# Optocouplers.net
KiCad netlist of a schematic drawn in Altium Designer
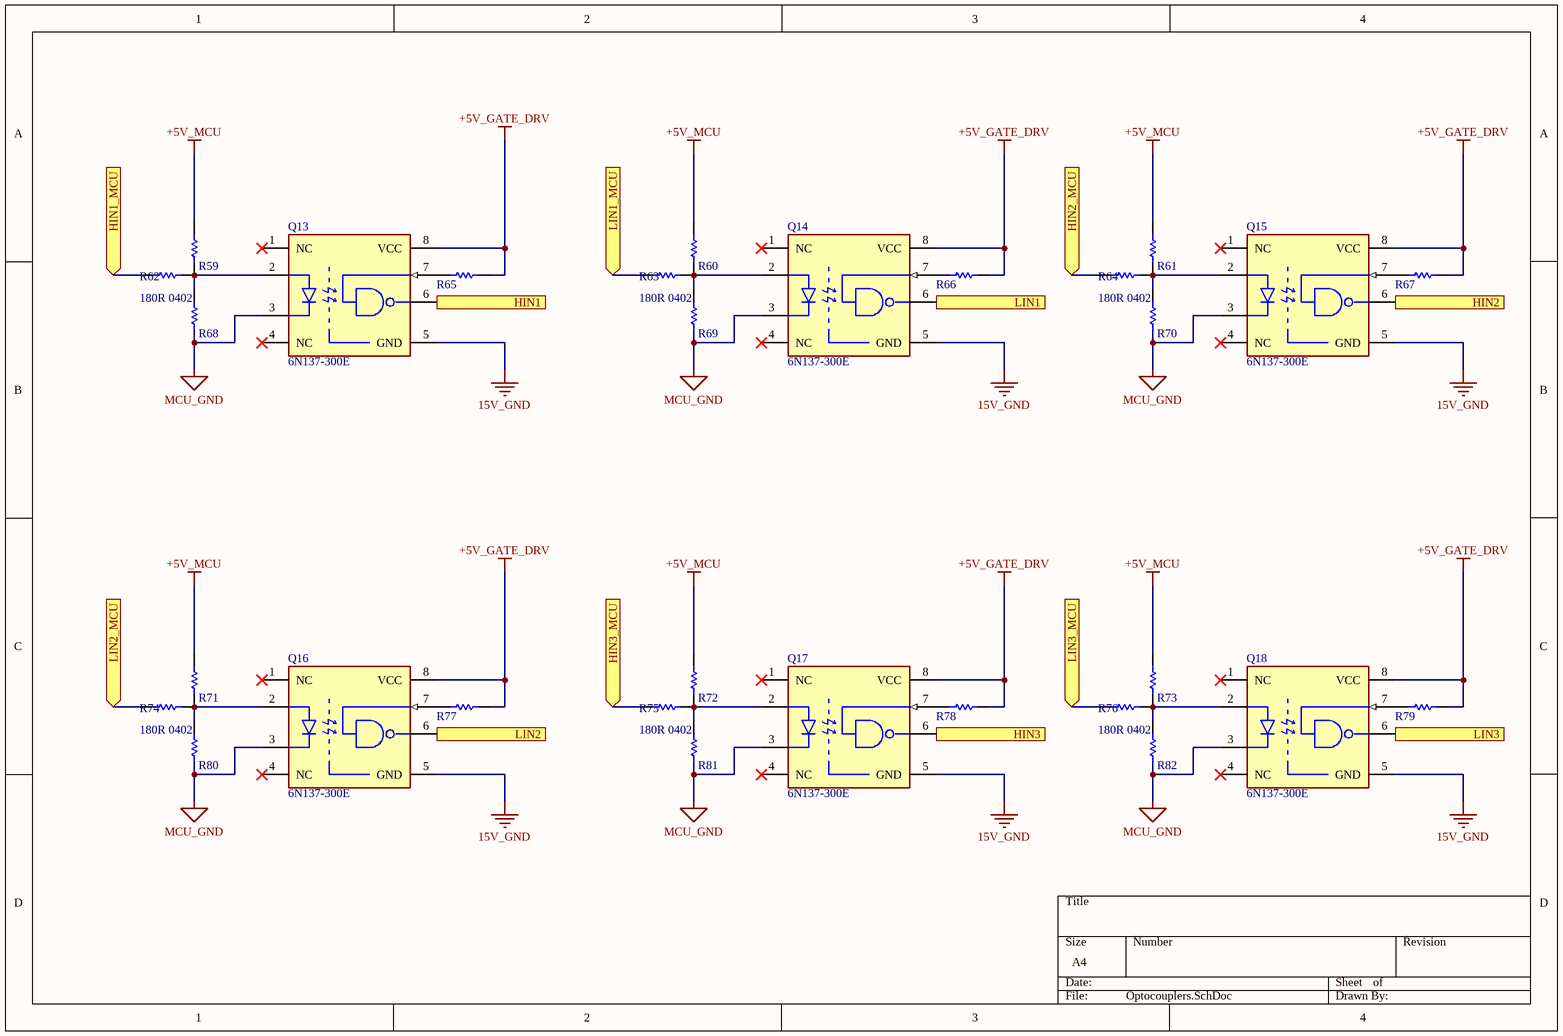
[diagram p0: Optocouplers.SchDoc]

(export (version "E")
  (design (tool "Eeschema 10.0.6"))
  (components
    (comp (ref "Q13")
      (value "6N137-300E")
      (footprint "FP-6N137-300E-MFG")
      (description "6N137 – High-Speed Optocoupler-SOP8")
      (fields
        (field (name "MANUFACTURER") "Broadcom")
        (field (name "OCTOPART") "https://octopart.com/6n137-300e-broadcom-71125550")
      )
      (libsource (lib "Altium Content Vault") (part "086db94909ba3b4bba0ec19532872cc"))
    )
    (comp (ref "Q14")
      (value "6N137-300E")
      (footprint "FP-6N137-300E-MFG")
      (description "6N137 – High-Speed Optocoupler-SOP8")
      (fields
        (field (name "MANUFACTURER") "Broadcom")
        (field (name "OCTOPART") "https://octopart.com/6n137-300e-broadcom-71125550")
      )
      (libsource (lib "Altium Content Vault") (part "086db94909ba3b4bba0ec19532872cc"))
    )
    (comp (ref "Q15")
      (value "6N137-300E")
      (footprint "FP-6N137-300E-MFG")
      (description "6N137 – High-Speed Optocoupler-SOP8")
      (fields
        (field (name "MANUFACTURER") "Broadcom")
        (field (name "OCTOPART") "https://octopart.com/6n137-300e-broadcom-71125550")
      )
      (libsource (lib "Altium Content Vault") (part "086db94909ba3b4bba0ec19532872cc"))
    )
    (comp (ref "Q16")
      (value "6N137-300E")
      (footprint "FP-6N137-300E-MFG")
      (description "6N137 – High-Speed Optocoupler-SOP8")
      (fields
        (field (name "MANUFACTURER") "Broadcom")
        (field (name "OCTOPART") "https://octopart.com/6n137-300e-broadcom-71125550")
      )
      (libsource (lib "Altium Content Vault") (part "086db94909ba3b4bba0ec19532872cc"))
    )
    (comp (ref "Q17")
      (value "6N137-300E")
      (footprint "FP-6N137-300E-MFG")
      (description "6N137 – High-Speed Optocoupler-SOP8")
      (fields
        (field (name "MANUFACTURER") "Broadcom")
        (field (name "OCTOPART") "https://octopart.com/6n137-300e-broadcom-71125550")
      )
      (libsource (lib "Altium Content Vault") (part "086db94909ba3b4bba0ec19532872cc"))
    )
    (comp (ref "Q18")
      (value "6N137-300E")
      (footprint "FP-6N137-300E-MFG")
      (description "6N137 – High-Speed Optocoupler-SOP8")
      (fields
        (field (name "MANUFACTURER") "Broadcom")
        (field (name "OCTOPART") "https://octopart.com/6n137-300e-broadcom-71125550")
      )
      (libsource (lib "Altium Content Vault") (part "086db94909ba3b4bba0ec19532872cc"))
    )
    (comp (ref "R59")
      (value "0R 0603")
      (footprint "R0603")
      (description "0 Ohm 1/10 Watt Resistor 1% Tolerance RC0603FR-070RL – 0603 Package")
      (libsource (lib "1kW_BLDC_Controller") (part "R0000 0603"))
    )
    (comp (ref "R60")
      (value "0R 0603")
      (footprint "R0603")
      (description "0 Ohm 1/10 Watt Resistor 1% Tolerance RC0603FR-070RL – 0603 Package")
      (libsource (lib "1kW_BLDC_Controller") (part "R0000 0603"))
    )
    (comp (ref "R61")
      (value "0R 0603")
      (footprint "R0603")
      (description "0 Ohm 1/10 Watt Resistor 1% Tolerance RC0603FR-070RL – 0603 Package")
      (libsource (lib "1kW_BLDC_Controller") (part "R0000 0603"))
    )
    (comp (ref "R62")
      (value "180R 0402")
      (footprint "R08050402")
      (description "180 Ohm 1/4 Watt Resistor – 0402 Package")
      (libsource (lib "1kW_BLDC_Controller") (part "R0805-0402"))
    )
    (comp (ref "R63")
      (value "180R 0402")
      (footprint "R08050402")
      (description "180 Ohm 1/4 Watt Resistor – 0402 Package")
      (libsource (lib "1kW_BLDC_Controller") (part "R0805-0402"))
    )
    (comp (ref "R64")
      (value "180R 0402")
      (footprint "R08050402")
      (description "180 Ohm 1/4 Watt Resistor – 0402 Package")
      (libsource (lib "1kW_BLDC_Controller") (part "R0805-0402"))
    )
    (comp (ref "R65")
      (value "0R 0603")
      (footprint "R0603")
      (description "0 Ohm 1/10 Watt Resistor 1% Tolerance RC0603FR-070RL – 0603 Package")
      (libsource (lib "1kW_BLDC_Controller") (part "R0000 0603"))
    )
    (comp (ref "R66")
      (value "0R 0603")
      (footprint "R0603")
      (description "0 Ohm 1/10 Watt Resistor 1% Tolerance RC0603FR-070RL – 0603 Package")
      (libsource (lib "1kW_BLDC_Controller") (part "R0000 0603"))
    )
    (comp (ref "R67")
      (value "0R 0603")
      (footprint "R0603")
      (description "0 Ohm 1/10 Watt Resistor 1% Tolerance RC0603FR-070RL – 0603 Package")
      (libsource (lib "1kW_BLDC_Controller") (part "R0000 0603"))
    )
    (comp (ref "R68")
      (value "0R 0603")
      (footprint "R0603")
      (description "0 Ohm 1/10 Watt Resistor 1% Tolerance RC0603FR-070RL – 0603 Package")
      (libsource (lib "1kW_BLDC_Controller") (part "R0000 0603"))
    )
    (comp (ref "R69")
      (value "0R 0603")
      (footprint "R0603")
      (description "0 Ohm 1/10 Watt Resistor 1% Tolerance RC0603FR-070RL – 0603 Package")
      (libsource (lib "1kW_BLDC_Controller") (part "R0000 0603"))
    )
    (comp (ref "R70")
      (value "0R 0603")
      (footprint "R0603")
      (description "0 Ohm 1/10 Watt Resistor 1% Tolerance RC0603FR-070RL – 0603 Package")
      (libsource (lib "1kW_BLDC_Controller") (part "R0000 0603"))
    )
    (comp (ref "R71")
      (value "0R 0603")
      (footprint "R0603")
      (description "0 Ohm 1/10 Watt Resistor 1% Tolerance RC0603FR-070RL – 0603 Package")
      (libsource (lib "1kW_BLDC_Controller") (part "R0000 0603"))
    )
    (comp (ref "R72")
      (value "0R 0603")
      (footprint "R0603")
      (description "0 Ohm 1/10 Watt Resistor 1% Tolerance RC0603FR-070RL – 0603 Package")
      (libsource (lib "1kW_BLDC_Controller") (part "R0000 0603"))
    )
    (comp (ref "R73")
      (value "0R 0603")
      (footprint "R0603")
      (description "0 Ohm 1/10 Watt Resistor 1% Tolerance RC0603FR-070RL – 0603 Package")
      (libsource (lib "1kW_BLDC_Controller") (part "R0000 0603"))
    )
    (comp (ref "R74")
      (value "180R 0402")
      (footprint "R08050402")
      (description "180 Ohm 1/4 Watt Resistor – 0402 Package")
      (libsource (lib "1kW_BLDC_Controller") (part "R0805-0402"))
    )
    (comp (ref "R75")
      (value "180R 0402")
      (footprint "R08050402")
      (description "180 Ohm 1/4 Watt Resistor – 0402 Package")
      (libsource (lib "1kW_BLDC_Controller") (part "R0805-0402"))
    )
    (comp (ref "R76")
      (value "180R 0402")
      (footprint "R08050402")
      (description "180 Ohm 1/4 Watt Resistor – 0402 Package")
      (libsource (lib "1kW_BLDC_Controller") (part "R0805-0402"))
    )
    (comp (ref "R77")
      (value "0R 0603")
      (footprint "R0603")
      (description "0 Ohm 1/10 Watt Resistor 1% Tolerance RC0603FR-070RL – 0603 Package")
      (libsource (lib "1kW_BLDC_Controller") (part "R0000 0603"))
    )
    (comp (ref "R78")
      (value "0R 0603")
      (footprint "R0603")
      (description "0 Ohm 1/10 Watt Resistor 1% Tolerance RC0603FR-070RL – 0603 Package")
      (libsource (lib "1kW_BLDC_Controller") (part "R0000 0603"))
    )
    (comp (ref "R79")
      (value "0R 0603")
      (footprint "R0603")
      (description "0 Ohm 1/10 Watt Resistor 1% Tolerance RC0603FR-070RL – 0603 Package")
      (libsource (lib "1kW_BLDC_Controller") (part "R0000 0603"))
    )
    (comp (ref "R80")
      (value "0R 0603")
      (footprint "R0603")
      (description "0 Ohm 1/10 Watt Resistor 1% Tolerance RC0603FR-070RL – 0603 Package")
      (libsource (lib "1kW_BLDC_Controller") (part "R0000 0603"))
    )
    (comp (ref "R81")
      (value "0R 0603")
      (footprint "R0603")
      (description "0 Ohm 1/10 Watt Resistor 1% Tolerance RC0603FR-070RL – 0603 Package")
      (libsource (lib "1kW_BLDC_Controller") (part "R0000 0603"))
    )
    (comp (ref "R82")
      (value "0R 0603")
      (footprint "R0603")
      (description "0 Ohm 1/10 Watt Resistor 1% Tolerance RC0603FR-070RL – 0603 Package")
      (libsource (lib "1kW_BLDC_Controller") (part "R0000 0603"))
    )
  )
  (nets
    (net (code "1") (name "+5V_GATE_DRV") (class "Default")
      (node (ref "Q13") (pin "8") (pinfunction "VCC_8") (pintype "power_in"))
      (node (ref "Q14") (pin "8") (pinfunction "VCC_8") (pintype "power_in"))
      (node (ref "Q15") (pin "8") (pinfunction "VCC_8") (pintype "power_in"))
      (node (ref "Q16") (pin "8") (pinfunction "VCC_8") (pintype "power_in"))
      (node (ref "Q17") (pin "8") (pinfunction "VCC_8") (pintype "power_in"))
      (node (ref "Q18") (pin "8") (pinfunction "VCC_8") (pintype "power_in"))
      (node (ref "R65") (pin "2") (pinfunction "2_2") (pintype "passive"))
      (node (ref "R66") (pin "2") (pinfunction "2_2") (pintype "passive"))
      (node (ref "R67") (pin "2") (pinfunction "2_2") (pintype "passive"))
      (node (ref "R77") (pin "2") (pinfunction "2_2") (pintype "passive"))
      (node (ref "R78") (pin "2") (pinfunction "2_2") (pintype "passive"))
      (node (ref "R79") (pin "2") (pinfunction "2_2") (pintype "passive"))
    )
    (net (code "2") (name "+5V_MCU") (class "Default")
      (node (ref "R59") (pin "2") (pinfunction "2_2") (pintype "passive"))
      (node (ref "R60") (pin "2") (pinfunction "2_2") (pintype "passive"))
      (node (ref "R61") (pin "2") (pinfunction "2_2") (pintype "passive"))
      (node (ref "R71") (pin "2") (pinfunction "2_2") (pintype "passive"))
      (node (ref "R72") (pin "2") (pinfunction "2_2") (pintype "passive"))
      (node (ref "R73") (pin "2") (pinfunction "2_2") (pintype "passive"))
    )
    (net (code "3") (name "/HIN1") (class "Default")
      (node (ref "Q13") (pin "6") (pinfunction "VO_6") (pintype "open_collector"))
    )
    (net (code "4") (name "/HIN1_MCU") (class "Default")
      (node (ref "R62") (pin "1") (pinfunction "1_1") (pintype "passive"))
    )
    (net (code "5") (name "/HIN2") (class "Default")
      (node (ref "Q15") (pin "6") (pinfunction "VO_6") (pintype "open_collector"))
    )
    (net (code "6") (name "/HIN2_MCU") (class "Default")
      (node (ref "R64") (pin "1") (pinfunction "1_1") (pintype "passive"))
    )
    (net (code "7") (name "/HIN3") (class "Default")
      (node (ref "Q17") (pin "6") (pinfunction "VO_6") (pintype "open_collector"))
    )
    (net (code "8") (name "/HIN3_MCU") (class "Default")
      (node (ref "R75") (pin "1") (pinfunction "1_1") (pintype "passive"))
    )
    (net (code "9") (name "/LIN1") (class "Default")
      (node (ref "Q14") (pin "6") (pinfunction "VO_6") (pintype "open_collector"))
    )
    (net (code "10") (name "/LIN1_MCU") (class "Default")
      (node (ref "R63") (pin "1") (pinfunction "1_1") (pintype "passive"))
    )
    (net (code "11") (name "/LIN2") (class "Default")
      (node (ref "Q16") (pin "6") (pinfunction "VO_6") (pintype "open_collector"))
    )
    (net (code "12") (name "/LIN2_MCU") (class "Default")
      (node (ref "R74") (pin "1") (pinfunction "1_1") (pintype "passive"))
    )
    (net (code "13") (name "/LIN3") (class "Default")
      (node (ref "Q18") (pin "6") (pinfunction "VO_6") (pintype "open_collector"))
    )
    (net (code "14") (name "/LIN3_MCU") (class "Default")
      (node (ref "R76") (pin "1") (pinfunction "1_1") (pintype "passive"))
    )
    (net (code "15") (name "15V_GND") (class "Default")
      (node (ref "Q13") (pin "5") (pinfunction "GND_5") (pintype "power_in"))
      (node (ref "Q14") (pin "5") (pinfunction "GND_5") (pintype "power_in"))
      (node (ref "Q15") (pin "5") (pinfunction "GND_5") (pintype "power_in"))
      (node (ref "Q16") (pin "5") (pinfunction "GND_5") (pintype "power_in"))
      (node (ref "Q17") (pin "5") (pinfunction "GND_5") (pintype "power_in"))
      (node (ref "Q18") (pin "5") (pinfunction "GND_5") (pintype "power_in"))
    )
    (net (code "16") (name "MCU_GND") (class "Default")
      (node (ref "Q13") (pin "3") (pinfunction "C_3") (pintype "passive"))
      (node (ref "Q14") (pin "3") (pinfunction "C_3") (pintype "passive"))
      (node (ref "Q15") (pin "3") (pinfunction "C_3") (pintype "passive"))
      (node (ref "Q16") (pin "3") (pinfunction "C_3") (pintype "passive"))
      (node (ref "Q17") (pin "3") (pinfunction "C_3") (pintype "passive"))
      (node (ref "Q18") (pin "3") (pinfunction "C_3") (pintype "passive"))
      (node (ref "R68") (pin "1") (pinfunction "1_1") (pintype "passive"))
      (node (ref "R69") (pin "1") (pinfunction "1_1") (pintype "passive"))
      (node (ref "R70") (pin "1") (pinfunction "1_1") (pintype "passive"))
      (node (ref "R80") (pin "1") (pinfunction "1_1") (pintype "passive"))
      (node (ref "R81") (pin "1") (pinfunction "1_1") (pintype "passive"))
      (node (ref "R82") (pin "1") (pinfunction "1_1") (pintype "passive"))
    )
    (net (code "17") (name "Net-(Q13-A)") (class "Default")
      (node (ref "Q13") (pin "2") (pinfunction "A_2") (pintype "passive"))
      (node (ref "R59") (pin "1") (pinfunction "1_1") (pintype "passive"))
      (node (ref "R62") (pin "2") (pinfunction "2_2") (pintype "passive"))
      (node (ref "R68") (pin "2") (pinfunction "2_2") (pintype "passive"))
    )
    (net (code "18") (name "Net-(Q13-VE)") (class "Default")
      (node (ref "Q13") (pin "7") (pinfunction "VE_7") (pintype "input"))
      (node (ref "R65") (pin "1") (pinfunction "1_1") (pintype "passive"))
    )
    (net (code "19") (name "Net-(Q14-A)") (class "Default")
      (node (ref "Q14") (pin "2") (pinfunction "A_2") (pintype "passive"))
      (node (ref "R60") (pin "1") (pinfunction "1_1") (pintype "passive"))
      (node (ref "R63") (pin "2") (pinfunction "2_2") (pintype "passive"))
      (node (ref "R69") (pin "2") (pinfunction "2_2") (pintype "passive"))
    )
    (net (code "20") (name "Net-(Q14-VE)") (class "Default")
      (node (ref "Q14") (pin "7") (pinfunction "VE_7") (pintype "input"))
      (node (ref "R66") (pin "1") (pinfunction "1_1") (pintype "passive"))
    )
    (net (code "21") (name "Net-(Q15-A)") (class "Default")
      (node (ref "Q15") (pin "2") (pinfunction "A_2") (pintype "passive"))
      (node (ref "R61") (pin "1") (pinfunction "1_1") (pintype "passive"))
      (node (ref "R64") (pin "2") (pinfunction "2_2") (pintype "passive"))
      (node (ref "R70") (pin "2") (pinfunction "2_2") (pintype "passive"))
    )
    (net (code "22") (name "Net-(Q15-VE)") (class "Default")
      (node (ref "Q15") (pin "7") (pinfunction "VE_7") (pintype "input"))
      (node (ref "R67") (pin "1") (pinfunction "1_1") (pintype "passive"))
    )
    (net (code "23") (name "Net-(Q16-A)") (class "Default")
      (node (ref "Q16") (pin "2") (pinfunction "A_2") (pintype "passive"))
      (node (ref "R71") (pin "1") (pinfunction "1_1") (pintype "passive"))
      (node (ref "R74") (pin "2") (pinfunction "2_2") (pintype "passive"))
      (node (ref "R80") (pin "2") (pinfunction "2_2") (pintype "passive"))
    )
    (net (code "24") (name "Net-(Q16-VE)") (class "Default")
      (node (ref "Q16") (pin "7") (pinfunction "VE_7") (pintype "input"))
      (node (ref "R77") (pin "1") (pinfunction "1_1") (pintype "passive"))
    )
    (net (code "25") (name "Net-(Q17-A)") (class "Default")
      (node (ref "Q17") (pin "2") (pinfunction "A_2") (pintype "passive"))
      (node (ref "R72") (pin "1") (pinfunction "1_1") (pintype "passive"))
      (node (ref "R75") (pin "2") (pinfunction "2_2") (pintype "passive"))
      (node (ref "R81") (pin "2") (pinfunction "2_2") (pintype "passive"))
    )
    (net (code "26") (name "Net-(Q17-VE)") (class "Default")
      (node (ref "Q17") (pin "7") (pinfunction "VE_7") (pintype "input"))
      (node (ref "R78") (pin "1") (pinfunction "1_1") (pintype "passive"))
    )
    (net (code "27") (name "Net-(Q18-A)") (class "Default")
      (node (ref "Q18") (pin "2") (pinfunction "A_2") (pintype "passive"))
      (node (ref "R73") (pin "1") (pinfunction "1_1") (pintype "passive"))
      (node (ref "R76") (pin "2") (pinfunction "2_2") (pintype "passive"))
      (node (ref "R82") (pin "2") (pinfunction "2_2") (pintype "passive"))
    )
    (net (code "28") (name "Net-(Q18-VE)") (class "Default")
      (node (ref "Q18") (pin "7") (pinfunction "VE_7") (pintype "input"))
      (node (ref "R79") (pin "1") (pinfunction "1_1") (pintype "passive"))
    )
    (net (code "29") (name "unconnected-(Q13-NC-Pad1)") (class "Default")
      (node (ref "Q13") (pin "1") (pinfunction "NC_1") (pintype "passive+no_connect"))
    )
    (net (code "30") (name "unconnected-(Q13-NC-Pad4)") (class "Default")
      (node (ref "Q13") (pin "4") (pinfunction "NC_4") (pintype "passive+no_connect"))
    )
    (net (code "31") (name "unconnected-(Q14-NC-Pad1)") (class "Default")
      (node (ref "Q14") (pin "1") (pinfunction "NC_1") (pintype "passive+no_connect"))
    )
    (net (code "32") (name "unconnected-(Q14-NC-Pad4)") (class "Default")
      (node (ref "Q14") (pin "4") (pinfunction "NC_4") (pintype "passive+no_connect"))
    )
    (net (code "33") (name "unconnected-(Q15-NC-Pad1)") (class "Default")
      (node (ref "Q15") (pin "1") (pinfunction "NC_1") (pintype "passive+no_connect"))
    )
    (net (code "34") (name "unconnected-(Q15-NC-Pad4)") (class "Default")
      (node (ref "Q15") (pin "4") (pinfunction "NC_4") (pintype "passive+no_connect"))
    )
    (net (code "35") (name "unconnected-(Q16-NC-Pad1)") (class "Default")
      (node (ref "Q16") (pin "1") (pinfunction "NC_1") (pintype "passive+no_connect"))
    )
    (net (code "36") (name "unconnected-(Q16-NC-Pad4)") (class "Default")
      (node (ref "Q16") (pin "4") (pinfunction "NC_4") (pintype "passive+no_connect"))
    )
    (net (code "37") (name "unconnected-(Q17-NC-Pad1)") (class "Default")
      (node (ref "Q17") (pin "1") (pinfunction "NC_1") (pintype "passive+no_connect"))
    )
    (net (code "38") (name "unconnected-(Q17-NC-Pad4)") (class "Default")
      (node (ref "Q17") (pin "4") (pinfunction "NC_4") (pintype "passive+no_connect"))
    )
    (net (code "39") (name "unconnected-(Q18-NC-Pad1)") (class "Default")
      (node (ref "Q18") (pin "1") (pinfunction "NC_1") (pintype "passive+no_connect"))
    )
    (net (code "40") (name "unconnected-(Q18-NC-Pad4)") (class "Default")
      (node (ref "Q18") (pin "4") (pinfunction "NC_4") (pintype "passive+no_connect"))
    )
  )
)
